# MX4-7-9-ESP12.net
KiCad netlist of a schematic drawn in EAGLE
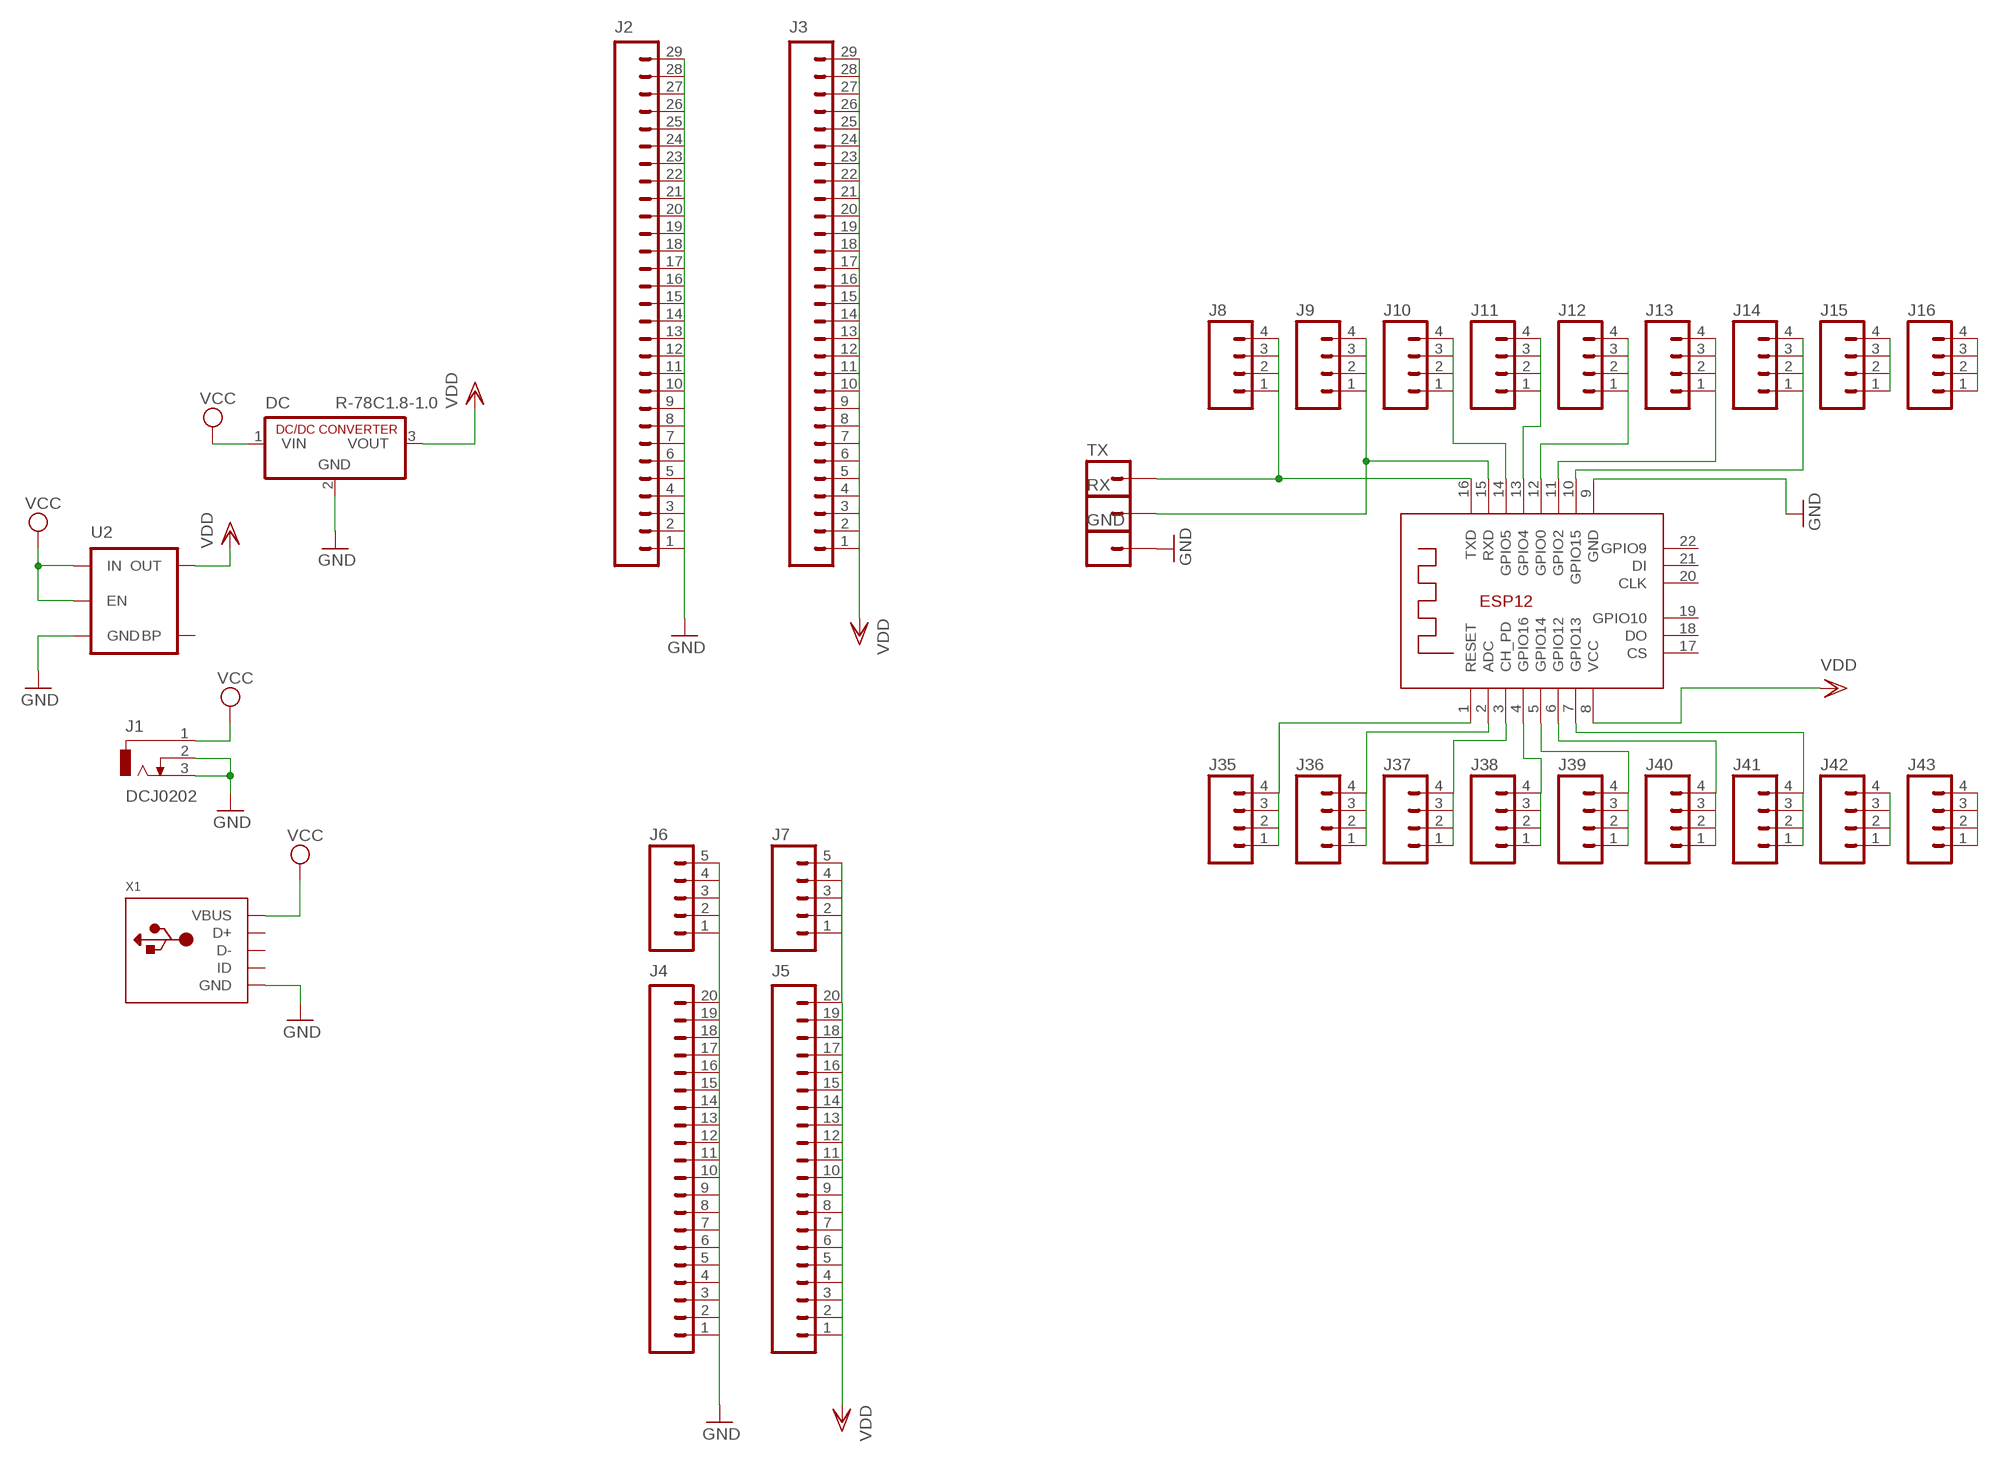
[diagram p0: schematic, sheet 1, part 1 of 2]
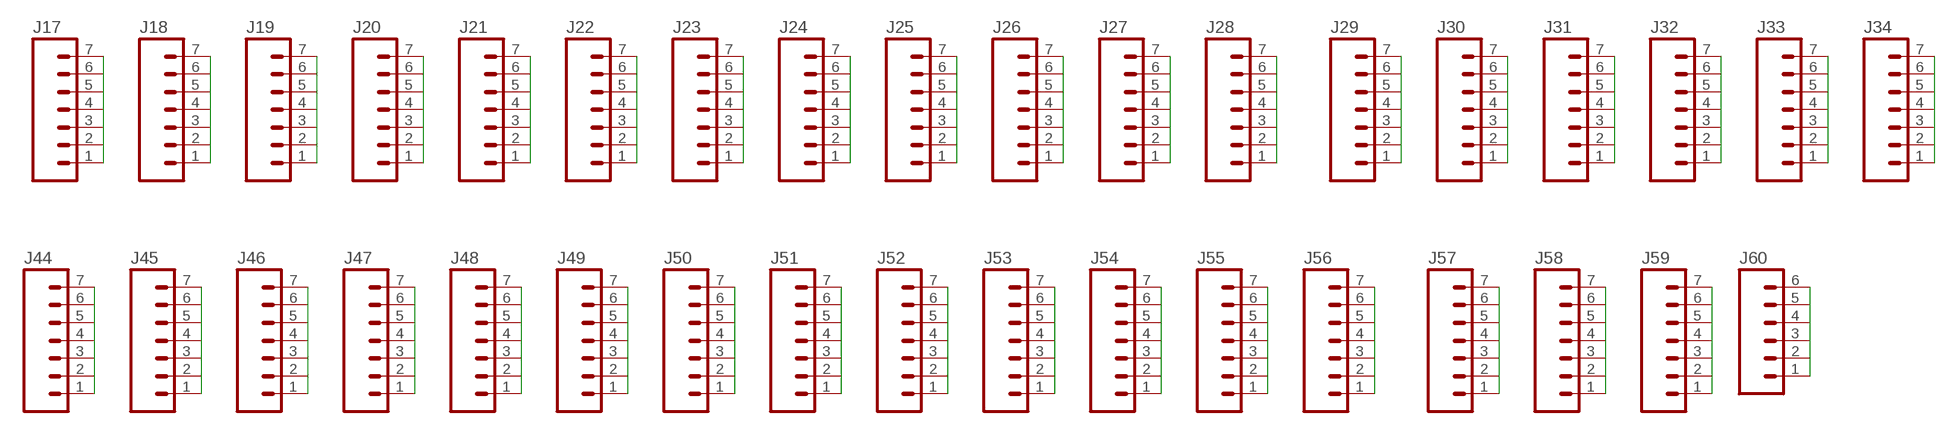
[diagram p1: schematic, sheet 1, part 2 of 2]

(export (version "E")
  (design (tool "Eeschema 10.0.6"))
  (components
    (comp (ref "DC")
      (value "R-78C1.8-1.0")
      (footprint "eagle-import:SIP3")
      (libsource (lib "eagle-import") (part "R-78C-1.01.8"))
    )
    (comp (ref "GND")
      (value "M01PTH_NO_SILK_YES_STOP")
      (footprint "eagle-import:1X01_NO_SILK")
      (libsource (lib "eagle-import") (part "M01PTH_NO_SILK_YES_STOP"))
    )
    (comp (ref "J1")
      (value "DCJ0202")
      (footprint "eagle-import:DCJ0202")
      (libsource (lib "eagle-import") (part "DCJ0202"))
    )
    (comp (ref "J2")
      (value "M29NO_SILK")
      (footprint "eagle-import:1X29_NO_SILK")
      (libsource (lib "eagle-import") (part "M29NO_SILK"))
    )
    (comp (ref "J3")
      (value "M29NO_SILK")
      (footprint "eagle-import:1X29_NO_SILK")
      (libsource (lib "eagle-import") (part "M29NO_SILK"))
    )
    (comp (ref "J4")
      (value "M20NO_SILK_KIT")
      (footprint "eagle-import:1X20_NO_SILK_KIT")
      (libsource (lib "eagle-import") (part "M20NO_SILK_KIT"))
    )
    (comp (ref "J5")
      (value "M20NO_SILK_KIT")
      (footprint "eagle-import:1X20_NO_SILK_KIT")
      (libsource (lib "eagle-import") (part "M20NO_SILK_KIT"))
    )
    (comp (ref "J6")
      (value "M05NO_SILK")
      (footprint "eagle-import:1X05_NO_SILK")
      (libsource (lib "eagle-import") (part "M05NO_SILK"))
    )
    (comp (ref "J7")
      (value "M05NO_SILK")
      (footprint "eagle-import:1X05_NO_SILK")
      (libsource (lib "eagle-import") (part "M05NO_SILK"))
    )
    (comp (ref "J8")
      (value "M04NO_SILK_ALL_ROUND")
      (footprint "eagle-import:1X04_NO_SILK_ALL_ROUND")
      (libsource (lib "eagle-import") (part "M04NO_SILK_ALL_ROUND"))
    )
    (comp (ref "J9")
      (value "M04NO_SILK_ALL_ROUND")
      (footprint "eagle-import:1X04_NO_SILK_ALL_ROUND")
      (libsource (lib "eagle-import") (part "M04NO_SILK_ALL_ROUND"))
    )
    (comp (ref "J10")
      (value "M04NO_SILK_ALL_ROUND")
      (footprint "eagle-import:1X04_NO_SILK_ALL_ROUND")
      (libsource (lib "eagle-import") (part "M04NO_SILK_ALL_ROUND"))
    )
    (comp (ref "J11")
      (value "M04NO_SILK_ALL_ROUND")
      (footprint "eagle-import:1X04_NO_SILK_ALL_ROUND")
      (libsource (lib "eagle-import") (part "M04NO_SILK_ALL_ROUND"))
    )
    (comp (ref "J12")
      (value "M04NO_SILK_ALL_ROUND")
      (footprint "eagle-import:1X04_NO_SILK_ALL_ROUND")
      (libsource (lib "eagle-import") (part "M04NO_SILK_ALL_ROUND"))
    )
    (comp (ref "J13")
      (value "M04NO_SILK_ALL_ROUND")
      (footprint "eagle-import:1X04_NO_SILK_ALL_ROUND")
      (libsource (lib "eagle-import") (part "M04NO_SILK_ALL_ROUND"))
    )
    (comp (ref "J14")
      (value "M04NO_SILK_ALL_ROUND")
      (footprint "eagle-import:1X04_NO_SILK_ALL_ROUND")
      (libsource (lib "eagle-import") (part "M04NO_SILK_ALL_ROUND"))
    )
    (comp (ref "J15")
      (value "M04NO_SILK_ALL_ROUND")
      (footprint "eagle-import:1X04_NO_SILK_ALL_ROUND")
      (libsource (lib "eagle-import") (part "M04NO_SILK_ALL_ROUND"))
    )
    (comp (ref "J16")
      (value "M04NO_SILK_ALL_ROUND")
      (footprint "eagle-import:1X04_NO_SILK_ALL_ROUND")
      (libsource (lib "eagle-import") (part "M04NO_SILK_ALL_ROUND"))
    )
    (comp (ref "J17")
      (value "M07NO_SILK")
      (footprint "eagle-import:1X07_NO_SILK")
      (libsource (lib "eagle-import") (part "M07NO_SILK"))
    )
    (comp (ref "J18")
      (value "M07NO_SILK")
      (footprint "eagle-import:1X07_NO_SILK")
      (libsource (lib "eagle-import") (part "M07NO_SILK"))
    )
    (comp (ref "J19")
      (value "M07NO_SILK")
      (footprint "eagle-import:1X07_NO_SILK")
      (libsource (lib "eagle-import") (part "M07NO_SILK"))
    )
    (comp (ref "J20")
      (value "M07NO_SILK")
      (footprint "eagle-import:1X07_NO_SILK")
      (libsource (lib "eagle-import") (part "M07NO_SILK"))
    )
    (comp (ref "J21")
      (value "M07NO_SILK")
      (footprint "eagle-import:1X07_NO_SILK")
      (libsource (lib "eagle-import") (part "M07NO_SILK"))
    )
    (comp (ref "J22")
      (value "M07NO_SILK")
      (footprint "eagle-import:1X07_NO_SILK")
      (libsource (lib "eagle-import") (part "M07NO_SILK"))
    )
    (comp (ref "J23")
      (value "M07NO_SILK")
      (footprint "eagle-import:1X07_NO_SILK")
      (libsource (lib "eagle-import") (part "M07NO_SILK"))
    )
    (comp (ref "J24")
      (value "M07NO_SILK")
      (footprint "eagle-import:1X07_NO_SILK")
      (libsource (lib "eagle-import") (part "M07NO_SILK"))
    )
    (comp (ref "J25")
      (value "M07NO_SILK")
      (footprint "eagle-import:1X07_NO_SILK")
      (libsource (lib "eagle-import") (part "M07NO_SILK"))
    )
    (comp (ref "J26")
      (value "M07NO_SILK")
      (footprint "eagle-import:1X07_NO_SILK")
      (libsource (lib "eagle-import") (part "M07NO_SILK"))
    )
    (comp (ref "J27")
      (value "M07NO_SILK")
      (footprint "eagle-import:1X07_NO_SILK")
      (libsource (lib "eagle-import") (part "M07NO_SILK"))
    )
    (comp (ref "J28")
      (value "M07NO_SILK")
      (footprint "eagle-import:1X07_NO_SILK")
      (libsource (lib "eagle-import") (part "M07NO_SILK"))
    )
    (comp (ref "J29")
      (value "M07NO_SILK")
      (footprint "eagle-import:1X07_NO_SILK")
      (libsource (lib "eagle-import") (part "M07NO_SILK"))
    )
    (comp (ref "J30")
      (value "M07NO_SILK")
      (footprint "eagle-import:1X07_NO_SILK")
      (libsource (lib "eagle-import") (part "M07NO_SILK"))
    )
    (comp (ref "J31")
      (value "M07NO_SILK")
      (footprint "eagle-import:1X07_NO_SILK")
      (libsource (lib "eagle-import") (part "M07NO_SILK"))
    )
    (comp (ref "J32")
      (value "M07NO_SILK")
      (footprint "eagle-import:1X07_NO_SILK")
      (libsource (lib "eagle-import") (part "M07NO_SILK"))
    )
    (comp (ref "J33")
      (value "M07NO_SILK")
      (footprint "eagle-import:1X07_NO_SILK")
      (libsource (lib "eagle-import") (part "M07NO_SILK"))
    )
    (comp (ref "J34")
      (value "M07NO_SILK")
      (footprint "eagle-import:1X07_NO_SILK")
      (libsource (lib "eagle-import") (part "M07NO_SILK"))
    )
    (comp (ref "J35")
      (value "M04NO_SILK_ALL_ROUND")
      (footprint "eagle-import:1X04_NO_SILK_ALL_ROUND")
      (libsource (lib "eagle-import") (part "M04NO_SILK_ALL_ROUND"))
    )
    (comp (ref "J36")
      (value "M04NO_SILK_ALL_ROUND")
      (footprint "eagle-import:1X04_NO_SILK_ALL_ROUND")
      (libsource (lib "eagle-import") (part "M04NO_SILK_ALL_ROUND"))
    )
    (comp (ref "J37")
      (value "M04NO_SILK_ALL_ROUND")
      (footprint "eagle-import:1X04_NO_SILK_ALL_ROUND")
      (libsource (lib "eagle-import") (part "M04NO_SILK_ALL_ROUND"))
    )
    (comp (ref "J38")
      (value "M04NO_SILK_ALL_ROUND")
      (footprint "eagle-import:1X04_NO_SILK_ALL_ROUND")
      (libsource (lib "eagle-import") (part "M04NO_SILK_ALL_ROUND"))
    )
    (comp (ref "J39")
      (value "M04NO_SILK_ALL_ROUND")
      (footprint "eagle-import:1X04_NO_SILK_ALL_ROUND")
      (libsource (lib "eagle-import") (part "M04NO_SILK_ALL_ROUND"))
    )
    (comp (ref "J40")
      (value "M04NO_SILK_ALL_ROUND")
      (footprint "eagle-import:1X04_NO_SILK_ALL_ROUND")
      (libsource (lib "eagle-import") (part "M04NO_SILK_ALL_ROUND"))
    )
    (comp (ref "J41")
      (value "M04NO_SILK_ALL_ROUND")
      (footprint "eagle-import:1X04_NO_SILK_ALL_ROUND")
      (libsource (lib "eagle-import") (part "M04NO_SILK_ALL_ROUND"))
    )
    (comp (ref "J42")
      (value "M04NO_SILK_ALL_ROUND")
      (footprint "eagle-import:1X04_NO_SILK_ALL_ROUND")
      (libsource (lib "eagle-import") (part "M04NO_SILK_ALL_ROUND"))
    )
    (comp (ref "J43")
      (value "M04NO_SILK_ALL_ROUND")
      (footprint "eagle-import:1X04_NO_SILK_ALL_ROUND")
      (libsource (lib "eagle-import") (part "M04NO_SILK_ALL_ROUND"))
    )
    (comp (ref "J44")
      (value "M07NO_SILK")
      (footprint "eagle-import:1X07_NO_SILK")
      (libsource (lib "eagle-import") (part "M07NO_SILK"))
    )
    (comp (ref "J45")
      (value "M07NO_SILK")
      (footprint "eagle-import:1X07_NO_SILK")
      (libsource (lib "eagle-import") (part "M07NO_SILK"))
    )
    (comp (ref "J46")
      (value "M07NO_SILK")
      (footprint "eagle-import:1X07_NO_SILK")
      (libsource (lib "eagle-import") (part "M07NO_SILK"))
    )
    (comp (ref "J47")
      (value "M07NO_SILK")
      (footprint "eagle-import:1X07_NO_SILK")
      (libsource (lib "eagle-import") (part "M07NO_SILK"))
    )
    (comp (ref "J48")
      (value "M07NO_SILK")
      (footprint "eagle-import:1X07_NO_SILK")
      (libsource (lib "eagle-import") (part "M07NO_SILK"))
    )
    (comp (ref "J49")
      (value "M07NO_SILK")
      (footprint "eagle-import:1X07_NO_SILK")
      (libsource (lib "eagle-import") (part "M07NO_SILK"))
    )
    (comp (ref "J50")
      (value "M07NO_SILK")
      (footprint "eagle-import:1X07_NO_SILK")
      (libsource (lib "eagle-import") (part "M07NO_SILK"))
    )
    (comp (ref "J51")
      (value "M07NO_SILK")
      (footprint "eagle-import:1X07_NO_SILK")
      (libsource (lib "eagle-import") (part "M07NO_SILK"))
    )
    (comp (ref "J52")
      (value "M07NO_SILK")
      (footprint "eagle-import:1X07_NO_SILK")
      (libsource (lib "eagle-import") (part "M07NO_SILK"))
    )
    (comp (ref "J53")
      (value "M07NO_SILK")
      (footprint "eagle-import:1X07_NO_SILK")
      (libsource (lib "eagle-import") (part "M07NO_SILK"))
    )
    (comp (ref "J54")
      (value "M07NO_SILK")
      (footprint "eagle-import:1X07_NO_SILK")
      (libsource (lib "eagle-import") (part "M07NO_SILK"))
    )
    (comp (ref "J55")
      (value "M07NO_SILK")
      (footprint "eagle-import:1X07_NO_SILK")
      (libsource (lib "eagle-import") (part "M07NO_SILK"))
    )
    (comp (ref "J56")
      (value "M07NO_SILK")
      (footprint "eagle-import:1X07_NO_SILK")
      (libsource (lib "eagle-import") (part "M07NO_SILK"))
    )
    (comp (ref "J57")
      (value "M07NO_SILK")
      (footprint "eagle-import:1X07_NO_SILK")
      (libsource (lib "eagle-import") (part "M07NO_SILK"))
    )
    (comp (ref "J58")
      (value "M07NO_SILK")
      (footprint "eagle-import:1X07_NO_SILK")
      (libsource (lib "eagle-import") (part "M07NO_SILK"))
    )
    (comp (ref "J59")
      (value "M07NO_SILK")
      (footprint "eagle-import:1X07_NO_SILK")
      (libsource (lib "eagle-import") (part "M07NO_SILK"))
    )
    (comp (ref "J60")
      (value "M06NO_SILK_FEMALE_PTH")
      (footprint "eagle-import:1X06_NO_SILK")
      (libsource (lib "eagle-import") (part "M06NO_SILK_FEMALE_PTH"))
    )
    (comp (ref "RX")
      (value "M01PTH_NO_SILK_YES_STOP")
      (footprint "eagle-import:1X01_NO_SILK")
      (libsource (lib "eagle-import") (part "M01PTH_NO_SILK_YES_STOP"))
    )
    (comp (ref "TX")
      (value "M01PTH_NO_SILK_YES_STOP")
      (footprint "eagle-import:1X01_NO_SILK")
      (libsource (lib "eagle-import") (part "M01PTH_NO_SILK_YES_STOP"))
    )
    (comp (ref "U2")
      (value "MIC52053.3V")
      (footprint "eagle-import:SOT23-5")
      (libsource (lib "eagle-import") (part "MIC52053.3V"))
    )
    (comp (ref "X1")
      (value "USBMICRO_20329")
      (footprint "eagle-import:4UCONN_20329")
      (libsource (lib "eagle-import") (part "USBMICRO_20329"))
    )
    (comp (ref "X2")
      (value "ESP-12E")
      (footprint "eagle-import:ESP-12E")
      (libsource (lib "eagle-import") (part "ESP-12E"))
    )
  )
  (nets
    (net (code "1") (name "GND") (class "Default")
      (node (ref "DC") (pin "2") (pinfunction "GND_2") (pintype "passive"))
      (node (ref "GND") (pin "1") (pinfunction "1_1") (pintype "passive"))
      (node (ref "J1") (pin "2") (pinfunction "2_2") (pintype "passive"))
      (node (ref "J1") (pin "3") (pinfunction "3_3") (pintype "passive"))
      (node (ref "J2") (pin "1") (pinfunction "1_1") (pintype "passive"))
      (node (ref "J2") (pin "10") (pinfunction "10_10") (pintype "passive"))
      (node (ref "J2") (pin "11") (pinfunction "11_11") (pintype "passive"))
      (node (ref "J2") (pin "12") (pinfunction "12_12") (pintype "passive"))
      (node (ref "J2") (pin "13") (pinfunction "13_13") (pintype "passive"))
      (node (ref "J2") (pin "14") (pinfunction "14_14") (pintype "passive"))
      (node (ref "J2") (pin "15") (pinfunction "15_15") (pintype "passive"))
      (node (ref "J2") (pin "16") (pinfunction "16_16") (pintype "passive"))
      (node (ref "J2") (pin "17") (pinfunction "17_17") (pintype "passive"))
      (node (ref "J2") (pin "18") (pinfunction "18_18") (pintype "passive"))
      (node (ref "J2") (pin "19") (pinfunction "19_19") (pintype "passive"))
      (node (ref "J2") (pin "2") (pinfunction "2_2") (pintype "passive"))
      (node (ref "J2") (pin "20") (pinfunction "20_20") (pintype "passive"))
      (node (ref "J2") (pin "21") (pinfunction "21_21") (pintype "passive"))
      (node (ref "J2") (pin "22") (pinfunction "22_22") (pintype "passive"))
      (node (ref "J2") (pin "23") (pinfunction "23_23") (pintype "passive"))
      (node (ref "J2") (pin "24") (pinfunction "24_24") (pintype "passive"))
      (node (ref "J2") (pin "25") (pinfunction "25_25") (pintype "passive"))
      (node (ref "J2") (pin "26") (pinfunction "26_26") (pintype "passive"))
      (node (ref "J2") (pin "27") (pinfunction "27_27") (pintype "passive"))
      (node (ref "J2") (pin "28") (pinfunction "28_28") (pintype "passive"))
      (node (ref "J2") (pin "29") (pinfunction "29_29") (pintype "passive"))
      (node (ref "J2") (pin "3") (pinfunction "3_3") (pintype "passive"))
      (node (ref "J2") (pin "4") (pinfunction "4_4") (pintype "passive"))
      (node (ref "J2") (pin "5") (pinfunction "5_5") (pintype "passive"))
      (node (ref "J2") (pin "6") (pinfunction "6_6") (pintype "passive"))
      (node (ref "J2") (pin "7") (pinfunction "7_7") (pintype "passive"))
      (node (ref "J2") (pin "8") (pinfunction "8_8") (pintype "passive"))
      (node (ref "J2") (pin "9") (pinfunction "9_9") (pintype "passive"))
      (node (ref "J4") (pin "1") (pinfunction "1_1") (pintype "passive"))
      (node (ref "J4") (pin "10") (pinfunction "10_10") (pintype "passive"))
      (node (ref "J4") (pin "11") (pinfunction "11_11") (pintype "passive"))
      (node (ref "J4") (pin "12") (pinfunction "12_12") (pintype "passive"))
      (node (ref "J4") (pin "13") (pinfunction "13_13") (pintype "passive"))
      (node (ref "J4") (pin "14") (pinfunction "14_14") (pintype "passive"))
      (node (ref "J4") (pin "15") (pinfunction "15_15") (pintype "passive"))
      (node (ref "J4") (pin "16") (pinfunction "16_16") (pintype "passive"))
      (node (ref "J4") (pin "17") (pinfunction "17_17") (pintype "passive"))
      (node (ref "J4") (pin "18") (pinfunction "18_18") (pintype "passive"))
      (node (ref "J4") (pin "19") (pinfunction "19_19") (pintype "passive"))
      (node (ref "J4") (pin "2") (pinfunction "2_2") (pintype "passive"))
      (node (ref "J4") (pin "20") (pinfunction "20_20") (pintype "passive"))
      (node (ref "J4") (pin "3") (pinfunction "3_3") (pintype "passive"))
      (node (ref "J4") (pin "4") (pinfunction "4_4") (pintype "passive"))
      (node (ref "J4") (pin "5") (pinfunction "5_5") (pintype "passive"))
      (node (ref "J4") (pin "6") (pinfunction "6_6") (pintype "passive"))
      (node (ref "J4") (pin "7") (pinfunction "7_7") (pintype "passive"))
      (node (ref "J4") (pin "8") (pinfunction "8_8") (pintype "passive"))
      (node (ref "J4") (pin "9") (pinfunction "9_9") (pintype "passive"))
      (node (ref "J6") (pin "1") (pinfunction "1_1") (pintype "passive"))
      (node (ref "J6") (pin "2") (pinfunction "2_2") (pintype "passive"))
      (node (ref "J6") (pin "3") (pinfunction "3_3") (pintype "passive"))
      (node (ref "J6") (pin "4") (pinfunction "4_4") (pintype "passive"))
      (node (ref "J6") (pin "5") (pinfunction "5_5") (pintype "passive"))
      (node (ref "U2") (pin "2") (pinfunction "GND_2") (pintype "input"))
      (node (ref "X1") (pin "BASE@1") (pinfunction "GND_BASE@1") (pintype "power_in"))
      (node (ref "X1") (pin "BASE@2") (pinfunction "GND_BASE@2") (pintype "power_in"))
      (node (ref "X1") (pin "GND") (pinfunction "GND_GND") (pintype "power_in"))
      (node (ref "X1") (pin "SPRT@1") (pinfunction "GND_SPRT@1") (pintype "power_in"))
      (node (ref "X1") (pin "SPRT@2") (pinfunction "GND_SPRT@2") (pintype "power_in"))
      (node (ref "X1") (pin "SPRT@3") (pinfunction "GND_SPRT@3") (pintype "power_in"))
      (node (ref "X1") (pin "SPRT@4") (pinfunction "GND_SPRT@4") (pintype "power_in"))
      (node (ref "X2") (pin "9") (pinfunction "GND_9") (pintype "power_in"))
    )
    (net (code "2") (name "Net-(J15-Pad1)") (class "Default")
      (node (ref "J15") (pin "1") (pinfunction "1_1") (pintype "passive"))
      (node (ref "J15") (pin "2") (pinfunction "2_2") (pintype "passive"))
      (node (ref "J15") (pin "3") (pinfunction "3_3") (pintype "passive"))
      (node (ref "J15") (pin "4") (pinfunction "4_4") (pintype "passive"))
    )
    (net (code "3") (name "Net-(J16-Pad1)") (class "Default")
      (node (ref "J16") (pin "1") (pinfunction "1_1") (pintype "passive"))
      (node (ref "J16") (pin "2") (pinfunction "2_2") (pintype "passive"))
      (node (ref "J16") (pin "3") (pinfunction "3_3") (pintype "passive"))
      (node (ref "J16") (pin "4") (pinfunction "4_4") (pintype "passive"))
    )
    (net (code "4") (name "Net-(J17-Pad1)") (class "Default")
      (node (ref "J17") (pin "1") (pinfunction "1_1") (pintype "passive"))
      (node (ref "J17") (pin "2") (pinfunction "2_2") (pintype "passive"))
      (node (ref "J17") (pin "3") (pinfunction "3_3") (pintype "passive"))
      (node (ref "J17") (pin "4") (pinfunction "4_4") (pintype "passive"))
      (node (ref "J17") (pin "5") (pinfunction "5_5") (pintype "passive"))
      (node (ref "J17") (pin "6") (pinfunction "6_6") (pintype "passive"))
      (node (ref "J17") (pin "7") (pinfunction "7_7") (pintype "passive"))
    )
    (net (code "5") (name "Net-(J18-Pad1)") (class "Default")
      (node (ref "J18") (pin "1") (pinfunction "1_1") (pintype "passive"))
      (node (ref "J18") (pin "2") (pinfunction "2_2") (pintype "passive"))
      (node (ref "J18") (pin "3") (pinfunction "3_3") (pintype "passive"))
      (node (ref "J18") (pin "4") (pinfunction "4_4") (pintype "passive"))
      (node (ref "J18") (pin "5") (pinfunction "5_5") (pintype "passive"))
      (node (ref "J18") (pin "6") (pinfunction "6_6") (pintype "passive"))
      (node (ref "J18") (pin "7") (pinfunction "7_7") (pintype "passive"))
    )
    (net (code "6") (name "Net-(J19-Pad1)") (class "Default")
      (node (ref "J19") (pin "1") (pinfunction "1_1") (pintype "passive"))
      (node (ref "J19") (pin "2") (pinfunction "2_2") (pintype "passive"))
      (node (ref "J19") (pin "3") (pinfunction "3_3") (pintype "passive"))
      (node (ref "J19") (pin "4") (pinfunction "4_4") (pintype "passive"))
      (node (ref "J19") (pin "5") (pinfunction "5_5") (pintype "passive"))
      (node (ref "J19") (pin "6") (pinfunction "6_6") (pintype "passive"))
      (node (ref "J19") (pin "7") (pinfunction "7_7") (pintype "passive"))
    )
    (net (code "7") (name "Net-(J20-Pad1)") (class "Default")
      (node (ref "J20") (pin "1") (pinfunction "1_1") (pintype "passive"))
      (node (ref "J20") (pin "2") (pinfunction "2_2") (pintype "passive"))
      (node (ref "J20") (pin "3") (pinfunction "3_3") (pintype "passive"))
      (node (ref "J20") (pin "4") (pinfunction "4_4") (pintype "passive"))
      (node (ref "J20") (pin "5") (pinfunction "5_5") (pintype "passive"))
      (node (ref "J20") (pin "6") (pinfunction "6_6") (pintype "passive"))
      (node (ref "J20") (pin "7") (pinfunction "7_7") (pintype "passive"))
    )
    (net (code "8") (name "Net-(J21-Pad1)") (class "Default")
      (node (ref "J21") (pin "1") (pinfunction "1_1") (pintype "passive"))
      (node (ref "J21") (pin "2") (pinfunction "2_2") (pintype "passive"))
      (node (ref "J21") (pin "3") (pinfunction "3_3") (pintype "passive"))
      (node (ref "J21") (pin "4") (pinfunction "4_4") (pintype "passive"))
      (node (ref "J21") (pin "5") (pinfunction "5_5") (pintype "passive"))
      (node (ref "J21") (pin "6") (pinfunction "6_6") (pintype "passive"))
      (node (ref "J21") (pin "7") (pinfunction "7_7") (pintype "passive"))
    )
    (net (code "9") (name "Net-(J22-Pad1)") (class "Default")
      (node (ref "J22") (pin "1") (pinfunction "1_1") (pintype "passive"))
      (node (ref "J22") (pin "2") (pinfunction "2_2") (pintype "passive"))
      (node (ref "J22") (pin "3") (pinfunction "3_3") (pintype "passive"))
      (node (ref "J22") (pin "4") (pinfunction "4_4") (pintype "passive"))
      (node (ref "J22") (pin "5") (pinfunction "5_5") (pintype "passive"))
      (node (ref "J22") (pin "6") (pinfunction "6_6") (pintype "passive"))
      (node (ref "J22") (pin "7") (pinfunction "7_7") (pintype "passive"))
    )
    (net (code "10") (name "Net-(J23-Pad1)") (class "Default")
      (node (ref "J23") (pin "1") (pinfunction "1_1") (pintype "passive"))
      (node (ref "J23") (pin "2") (pinfunction "2_2") (pintype "passive"))
      (node (ref "J23") (pin "3") (pinfunction "3_3") (pintype "passive"))
      (node (ref "J23") (pin "4") (pinfunction "4_4") (pintype "passive"))
      (node (ref "J23") (pin "5") (pinfunction "5_5") (pintype "passive"))
      (node (ref "J23") (pin "6") (pinfunction "6_6") (pintype "passive"))
      (node (ref "J23") (pin "7") (pinfunction "7_7") (pintype "passive"))
    )
    (net (code "11") (name "Net-(J24-Pad1)") (class "Default")
      (node (ref "J24") (pin "1") (pinfunction "1_1") (pintype "passive"))
      (node (ref "J24") (pin "2") (pinfunction "2_2") (pintype "passive"))
      (node (ref "J24") (pin "3") (pinfunction "3_3") (pintype "passive"))
      (node (ref "J24") (pin "4") (pinfunction "4_4") (pintype "passive"))
      (node (ref "J24") (pin "5") (pinfunction "5_5") (pintype "passive"))
      (node (ref "J24") (pin "6") (pinfunction "6_6") (pintype "passive"))
      (node (ref "J24") (pin "7") (pinfunction "7_7") (pintype "passive"))
    )
    (net (code "12") (name "Net-(J25-Pad1)") (class "Default")
      (node (ref "J25") (pin "1") (pinfunction "1_1") (pintype "passive"))
      (node (ref "J25") (pin "2") (pinfunction "2_2") (pintype "passive"))
      (node (ref "J25") (pin "3") (pinfunction "3_3") (pintype "passive"))
      (node (ref "J25") (pin "4") (pinfunction "4_4") (pintype "passive"))
      (node (ref "J25") (pin "5") (pinfunction "5_5") (pintype "passive"))
      (node (ref "J25") (pin "6") (pinfunction "6_6") (pintype "passive"))
      (node (ref "J25") (pin "7") (pinfunction "7_7") (pintype "passive"))
    )
    (net (code "13") (name "Net-(J26-Pad1)") (class "Default")
      (node (ref "J26") (pin "1") (pinfunction "1_1") (pintype "passive"))
      (node (ref "J26") (pin "2") (pinfunction "2_2") (pintype "passive"))
      (node (ref "J26") (pin "3") (pinfunction "3_3") (pintype "passive"))
      (node (ref "J26") (pin "4") (pinfunction "4_4") (pintype "passive"))
      (node (ref "J26") (pin "5") (pinfunction "5_5") (pintype "passive"))
      (node (ref "J26") (pin "6") (pinfunction "6_6") (pintype "passive"))
      (node (ref "J26") (pin "7") (pinfunction "7_7") (pintype "passive"))
    )
    (net (code "14") (name "Net-(J27-Pad1)") (class "Default")
      (node (ref "J27") (pin "1") (pinfunction "1_1") (pintype "passive"))
      (node (ref "J27") (pin "2") (pinfunction "2_2") (pintype "passive"))
      (node (ref "J27") (pin "3") (pinfunction "3_3") (pintype "passive"))
      (node (ref "J27") (pin "4") (pinfunction "4_4") (pintype "passive"))
      (node (ref "J27") (pin "5") (pinfunction "5_5") (pintype "passive"))
      (node (ref "J27") (pin "6") (pinfunction "6_6") (pintype "passive"))
      (node (ref "J27") (pin "7") (pinfunction "7_7") (pintype "passive"))
    )
    (net (code "15") (name "Net-(J28-Pad1)") (class "Default")
      (node (ref "J28") (pin "1") (pinfunction "1_1") (pintype "passive"))
      (node (ref "J28") (pin "2") (pinfunction "2_2") (pintype "passive"))
      (node (ref "J28") (pin "3") (pinfunction "3_3") (pintype "passive"))
      (node (ref "J28") (pin "4") (pinfunction "4_4") (pintype "passive"))
      (node (ref "J28") (pin "5") (pinfunction "5_5") (pintype "passive"))
      (node (ref "J28") (pin "6") (pinfunction "6_6") (pintype "passive"))
      (node (ref "J28") (pin "7") (pinfunction "7_7") (pintype "passive"))
    )
    (net (code "16") (name "Net-(J29-Pad1)") (class "Default")
      (node (ref "J29") (pin "1") (pinfunction "1_1") (pintype "passive"))
      (node (ref "J29") (pin "2") (pinfunction "2_2") (pintype "passive"))
      (node (ref "J29") (pin "3") (pinfunction "3_3") (pintype "passive"))
      (node (ref "J29") (pin "4") (pinfunction "4_4") (pintype "passive"))
      (node (ref "J29") (pin "5") (pinfunction "5_5") (pintype "passive"))
      (node (ref "J29") (pin "6") (pinfunction "6_6") (pintype "passive"))
      (node (ref "J29") (pin "7") (pinfunction "7_7") (pintype "passive"))
    )
    (net (code "17") (name "Net-(J30-Pad1)") (class "Default")
      (node (ref "J30") (pin "1") (pinfunction "1_1") (pintype "passive"))
      (node (ref "J30") (pin "2") (pinfunction "2_2") (pintype "passive"))
      (node (ref "J30") (pin "3") (pinfunction "3_3") (pintype "passive"))
      (node (ref "J30") (pin "4") (pinfunction "4_4") (pintype "passive"))
      (node (ref "J30") (pin "5") (pinfunction "5_5") (pintype "passive"))
      (node (ref "J30") (pin "6") (pinfunction "6_6") (pintype "passive"))
      (node (ref "J30") (pin "7") (pinfunction "7_7") (pintype "passive"))
    )
    (net (code "18") (name "Net-(J31-Pad1)") (class "Default")
      (node (ref "J31") (pin "1") (pinfunction "1_1") (pintype "passive"))
      (node (ref "J31") (pin "2") (pinfunction "2_2") (pintype "passive"))
      (node (ref "J31") (pin "3") (pinfunction "3_3") (pintype "passive"))
      (node (ref "J31") (pin "4") (pinfunction "4_4") (pintype "passive"))
      (node (ref "J31") (pin "5") (pinfunction "5_5") (pintype "passive"))
      (node (ref "J31") (pin "6") (pinfunction "6_6") (pintype "passive"))
      (node (ref "J31") (pin "7") (pinfunction "7_7") (pintype "passive"))
    )
    (net (code "19") (name "Net-(J32-Pad1)") (class "Default")
      (node (ref "J32") (pin "1") (pinfunction "1_1") (pintype "passive"))
      (node (ref "J32") (pin "2") (pinfunction "2_2") (pintype "passive"))
      (node (ref "J32") (pin "3") (pinfunction "3_3") (pintype "passive"))
      (node (ref "J32") (pin "4") (pinfunction "4_4") (pintype "passive"))
      (node (ref "J32") (pin "5") (pinfunction "5_5") (pintype "passive"))
      (node (ref "J32") (pin "6") (pinfunction "6_6") (pintype "passive"))
      (node (ref "J32") (pin "7") (pinfunction "7_7") (pintype "passive"))
    )
    (net (code "20") (name "Net-(J33-Pad1)") (class "Default")
      (node (ref "J33") (pin "1") (pinfunction "1_1") (pintype "passive"))
      (node (ref "J33") (pin "2") (pinfunction "2_2") (pintype "passive"))
      (node (ref "J33") (pin "3") (pinfunction "3_3") (pintype "passive"))
      (node (ref "J33") (pin "4") (pinfunction "4_4") (pintype "passive"))
      (node (ref "J33") (pin "5") (pinfunction "5_5") (pintype "passive"))
      (node (ref "J33") (pin "6") (pinfunction "6_6") (pintype "passive"))
      (node (ref "J33") (pin "7") (pinfunction "7_7") (pintype "passive"))
    )
    (net (code "21") (name "Net-(J34-Pad1)") (class "Default")
      (node (ref "J34") (pin "1") (pinfunction "1_1") (pintype "passive"))
      (node (ref "J34") (pin "2") (pinfunction "2_2") (pintype "passive"))
      (node (ref "J34") (pin "3") (pinfunction "3_3") (pintype "passive"))
      (node (ref "J34") (pin "4") (pinfunction "4_4") (pintype "passive"))
      (node (ref "J34") (pin "5") (pinfunction "5_5") (pintype "passive"))
      (node (ref "J34") (pin "6") (pinfunction "6_6") (pintype "passive"))
      (node (ref "J34") (pin "7") (pinfunction "7_7") (pintype "passive"))
    )
    (net (code "22") (name "Net-(J42-Pad1)") (class "Default")
      (node (ref "J42") (pin "1") (pinfunction "1_1") (pintype "passive"))
      (node (ref "J42") (pin "2") (pinfunction "2_2") (pintype "passive"))
      (node (ref "J42") (pin "3") (pinfunction "3_3") (pintype "passive"))
      (node (ref "J42") (pin "4") (pinfunction "4_4") (pintype "passive"))
    )
    (net (code "23") (name "Net-(J43-Pad1)") (class "Default")
      (node (ref "J43") (pin "1") (pinfunction "1_1") (pintype "passive"))
      (node (ref "J43") (pin "2") (pinfunction "2_2") (pintype "passive"))
      (node (ref "J43") (pin "3") (pinfunction "3_3") (pintype "passive"))
      (node (ref "J43") (pin "4") (pinfunction "4_4") (pintype "passive"))
    )
    (net (code "24") (name "Net-(J44-Pad1)") (class "Default")
      (node (ref "J44") (pin "1") (pinfunction "1_1") (pintype "passive"))
      (node (ref "J44") (pin "2") (pinfunction "2_2") (pintype "passive"))
      (node (ref "J44") (pin "3") (pinfunction "3_3") (pintype "passive"))
      (node (ref "J44") (pin "4") (pinfunction "4_4") (pintype "passive"))
      (node (ref "J44") (pin "5") (pinfunction "5_5") (pintype "passive"))
      (node (ref "J44") (pin "6") (pinfunction "6_6") (pintype "passive"))
      (node (ref "J44") (pin "7") (pinfunction "7_7") (pintype "passive"))
    )
    (net (code "25") (name "Net-(J45-Pad1)") (class "Default")
      (node (ref "J45") (pin "1") (pinfunction "1_1") (pintype "passive"))
      (node (ref "J45") (pin "2") (pinfunction "2_2") (pintype "passive"))
      (node (ref "J45") (pin "3") (pinfunction "3_3") (pintype "passive"))
      (node (ref "J45") (pin "4") (pinfunction "4_4") (pintype "passive"))
      (node (ref "J45") (pin "5") (pinfunction "5_5") (pintype "passive"))
      (node (ref "J45") (pin "6") (pinfunction "6_6") (pintype "passive"))
      (node (ref "J45") (pin "7") (pinfunction "7_7") (pintype "passive"))
    )
    (net (code "26") (name "Net-(J46-Pad1)") (class "Default")
      (node (ref "J46") (pin "1") (pinfunction "1_1") (pintype "passive"))
      (node (ref "J46") (pin "2") (pinfunction "2_2") (pintype "passive"))
      (node (ref "J46") (pin "3") (pinfunction "3_3") (pintype "passive"))
      (node (ref "J46") (pin "4") (pinfunction "4_4") (pintype "passive"))
      (node (ref "J46") (pin "5") (pinfunction "5_5") (pintype "passive"))
      (node (ref "J46") (pin "6") (pinfunction "6_6") (pintype "passive"))
      (node (ref "J46") (pin "7") (pinfunction "7_7") (pintype "passive"))
    )
    (net (code "27") (name "Net-(J47-Pad1)") (class "Default")
      (node (ref "J47") (pin "1") (pinfunction "1_1") (pintype "passive"))
      (node (ref "J47") (pin "2") (pinfunction "2_2") (pintype "passive"))
      (node (ref "J47") (pin "3") (pinfunction "3_3") (pintype "passive"))
      (node (ref "J47") (pin "4") (pinfunction "4_4") (pintype "passive"))
      (node (ref "J47") (pin "5") (pinfunction "5_5") (pintype "passive"))
      (node (ref "J47") (pin "6") (pinfunction "6_6") (pintype "passive"))
      (node (ref "J47") (pin "7") (pinfunction "7_7") (pintype "passive"))
    )
    (net (code "28") (name "Net-(J48-Pad1)") (class "Default")
      (node (ref "J48") (pin "1") (pinfunction "1_1") (pintype "passive"))
      (node (ref "J48") (pin "2") (pinfunction "2_2") (pintype "passive"))
      (node (ref "J48") (pin "3") (pinfunction "3_3") (pintype "passive"))
      (node (ref "J48") (pin "4") (pinfunction "4_4") (pintype "passive"))
      (node (ref "J48") (pin "5") (pinfunction "5_5") (pintype "passive"))
      (node (ref "J48") (pin "6") (pinfunction "6_6") (pintype "passive"))
      (node (ref "J48") (pin "7") (pinfunction "7_7") (pintype "passive"))
    )
    (net (code "29") (name "Net-(J49-Pad1)") (class "Default")
      (node (ref "J49") (pin "1") (pinfunction "1_1") (pintype "passive"))
      (node (ref "J49") (pin "2") (pinfunction "2_2") (pintype "passive"))
      (node (ref "J49") (pin "3") (pinfunction "3_3") (pintype "passive"))
      (node (ref "J49") (pin "4") (pinfunction "4_4") (pintype "passive"))
      (node (ref "J49") (pin "5") (pinfunction "5_5") (pintype "passive"))
      (node (ref "J49") (pin "6") (pinfunction "6_6") (pintype "passive"))
      (node (ref "J49") (pin "7") (pinfunction "7_7") (pintype "passive"))
    )
    (net (code "30") (name "Net-(J50-Pad1)") (class "Default")
      (node (ref "J50") (pin "1") (pinfunction "1_1") (pintype "passive"))
      (node (ref "J50") (pin "2") (pinfunction "2_2") (pintype "passive"))
      (node (ref "J50") (pin "3") (pinfunction "3_3") (pintype "passive"))
      (node (ref "J50") (pin "4") (pinfunction "4_4") (pintype "passive"))
      (node (ref "J50") (pin "5") (pinfunction "5_5") (pintype "passive"))
      (node (ref "J50") (pin "6") (pinfunction "6_6") (pintype "passive"))
      (node (ref "J50") (pin "7") (pinfunction "7_7") (pintype "passive"))
    )
    (net (code "31") (name "Net-(J51-Pad1)") (class "Default")
      (node (ref "J51") (pin "1") (pinfunction "1_1") (pintype "passive"))
      (node (ref "J51") (pin "2") (pinfunction "2_2") (pintype "passive"))
      (node (ref "J51") (pin "3") (pinfunction "3_3") (pintype "passive"))
      (node (ref "J51") (pin "4") (pinfunction "4_4") (pintype "passive"))
      (node (ref "J51") (pin "5") (pinfunction "5_5") (pintype "passive"))
      (node (ref "J51") (pin "6") (pinfunction "6_6") (pintype "passive"))
      (node (ref "J51") (pin "7") (pinfunction "7_7") (pintype "passive"))
    )
    (net (code "32") (name "Net-(J52-Pad1)") (class "Default")
      (node (ref "J52") (pin "1") (pinfunction "1_1") (pintype "passive"))
      (node (ref "J52") (pin "2") (pinfunction "2_2") (pintype "passive"))
      (node (ref "J52") (pin "3") (pinfunction "3_3") (pintype "passive"))
      (node (ref "J52") (pin "4") (pinfunction "4_4") (pintype "passive"))
      (node (ref "J52") (pin "5") (pinfunction "5_5") (pintype "passive"))
      (node (ref "J52") (pin "6") (pinfunction "6_6") (pintype "passive"))
      (node (ref "J52") (pin "7") (pinfunction "7_7") (pintype "passive"))
    )
    (net (code "33") (name "Net-(J53-Pad1)") (class "Default")
      (node (ref "J53") (pin "1") (pinfunction "1_1") (pintype "passive"))
      (node (ref "J53") (pin "2") (pinfunction "2_2") (pintype "passive"))
      (node (ref "J53") (pin "3") (pinfunction "3_3") (pintype "passive"))
      (node (ref "J53") (pin "4") (pinfunction "4_4") (pintype "passive"))
      (node (ref "J53") (pin "5") (pinfunction "5_5") (pintype "passive"))
      (node (ref "J53") (pin "6") (pinfunction "6_6") (pintype "passive"))
      (node (ref "J53") (pin "7") (pinfunction "7_7") (pintype "passive"))
    )
    (net (code "34") (name "Net-(J54-Pad1)") (class "Default")
      (node (ref "J54") (pin "1") (pinfunction "1_1") (pintype "passive"))
      (node (ref "J54") (pin "2") (pinfunction "2_2") (pintype "passive"))
      (node (ref "J54") (pin "3") (pinfunction "3_3") (pintype "passive"))
      (node (ref "J54") (pin "4") (pinfunction "4_4") (pintype "passive"))
      (node (ref "J54") (pin "5") (pinfunction "5_5") (pintype "passive"))
      (node (ref "J54") (pin "6") (pinfunction "6_6") (pintype "passive"))
      (node (ref "J54") (pin "7") (pinfunction "7_7") (pintype "passive"))
    )
    (net (code "35") (name "Net-(J55-Pad1)") (class "Default")
      (node (ref "J55") (pin "1") (pinfunction "1_1") (pintype "passive"))
      (node (ref "J55") (pin "2") (pinfunction "2_2") (pintype "passive"))
      (node (ref "J55") (pin "3") (pinfunction "3_3") (pintype "passive"))
      (node (ref "J55") (pin "4") (pinfunction "4_4") (pintype "passive"))
      (node (ref "J55") (pin "5") (pinfunction "5_5") (pintype "passive"))
      (node (ref "J55") (pin "6") (pinfunction "6_6") (pintype "passive"))
      (node (ref "J55") (pin "7") (pinfunction "7_7") (pintype "passive"))
    )
    (net (code "36") (name "Net-(J56-Pad1)") (class "Default")
      (node (ref "J56") (pin "1") (pinfunction "1_1") (pintype "passive"))
      (node (ref "J56") (pin "2") (pinfunction "2_2") (pintype "passive"))
      (node (ref "J56") (pin "3") (pinfunction "3_3") (pintype "passive"))
      (node (ref "J56") (pin "4") (pinfunction "4_4") (pintype "passive"))
      (node (ref "J56") (pin "5") (pinfunction "5_5") (pintype "passive"))
      (node (ref "J56") (pin "6") (pinfunction "6_6") (pintype "passive"))
      (node (ref "J56") (pin "7") (pinfunction "7_7") (pintype "passive"))
    )
    (net (code "37") (name "Net-(J57-Pad1)") (class "Default")
      (node (ref "J57") (pin "1") (pinfunction "1_1") (pintype "passive"))
      (node (ref "J57") (pin "2") (pinfunction "2_2") (pintype "passive"))
      (node (ref "J57") (pin "3") (pinfunction "3_3") (pintype "passive"))
      (node (ref "J57") (pin "4") (pinfunction "4_4") (pintype "passive"))
      (node (ref "J57") (pin "5") (pinfunction "5_5") (pintype "passive"))
      (node (ref "J57") (pin "6") (pinfunction "6_6") (pintype "passive"))
      (node (ref "J57") (pin "7") (pinfunction "7_7") (pintype "passive"))
    )
    (net (code "38") (name "Net-(J58-Pad1)") (class "Default")
      (node (ref "J58") (pin "1") (pinfunction "1_1") (pintype "passive"))
      (node (ref "J58") (pin "2") (pinfunction "2_2") (pintype "passive"))
      (node (ref "J58") (pin "3") (pinfunction "3_3") (pintype "passive"))
      (node (ref "J58") (pin "4") (pinfunction "4_4") (pintype "passive"))
      (node (ref "J58") (pin "5") (pinfunction "5_5") (pintype "passive"))
      (node (ref "J58") (pin "6") (pinfunction "6_6") (pintype "passive"))
      (node (ref "J58") (pin "7") (pinfunction "7_7") (pintype "passive"))
    )
    (net (code "39") (name "Net-(J59-Pad1)") (class "Default")
      (node (ref "J59") (pin "1") (pinfunction "1_1") (pintype "passive"))
      (node (ref "J59") (pin "2") (pinfunction "2_2") (pintype "passive"))
      (node (ref "J59") (pin "3") (pinfunction "3_3") (pintype "passive"))
      (node (ref "J59") (pin "4") (pinfunction "4_4") (pintype "passive"))
      (node (ref "J59") (pin "5") (pinfunction "5_5") (pintype "passive"))
      (node (ref "J59") (pin "6") (pinfunction "6_6") (pintype "passive"))
      (node (ref "J59") (pin "7") (pinfunction "7_7") (pintype "passive"))
    )
    (net (code "40") (name "Net-(J60-Pad1)") (class "Default")
      (node (ref "J60") (pin "1") (pinfunction "1_1") (pintype "passive"))
      (node (ref "J60") (pin "2") (pinfunction "2_2") (pintype "passive"))
      (node (ref "J60") (pin "3") (pinfunction "3_3") (pintype "passive"))
      (node (ref "J60") (pin "4") (pinfunction "4_4") (pintype "passive"))
      (node (ref "J60") (pin "5") (pinfunction "5_5") (pintype "passive"))
      (node (ref "J60") (pin "6") (pinfunction "6_6") (pintype "passive"))
    )
    (net (code "41") (name "Net-(X2-ADC)") (class "Default")
      (node (ref "J36") (pin "1") (pinfunction "1_1") (pintype "passive"))
      (node (ref "J36") (pin "2") (pinfunction "2_2") (pintype "passive"))
      (node (ref "J36") (pin "3") (pinfunction "3_3") (pintype "passive"))
      (node (ref "J36") (pin "4") (pinfunction "4_4") (pintype "passive"))
      (node (ref "X2") (pin "2") (pinfunction "ADC_2") (pintype "passive"))
    )
    (net (code "42") (name "Net-(X2-CH_PD)") (class "Default")
      (node (ref "J37") (pin "1") (pinfunction "1_1") (pintype "passive"))
      (node (ref "J37") (pin "2") (pinfunction "2_2") (pintype "passive"))
      (node (ref "J37") (pin "3") (pinfunction "3_3") (pintype "passive"))
      (node (ref "J37") (pin "4") (pinfunction "4_4") (pintype "passive"))
      (node (ref "X2") (pin "3") (pinfunction "CH_PD_3") (pintype "input"))
    )
    (net (code "43") (name "Net-(X2-GPIO0)") (class "Default")
      (node (ref "J12") (pin "1") (pinfunction "1_1") (pintype "passive"))
      (node (ref "J12") (pin "2") (pinfunction "2_2") (pintype "passive"))
      (node (ref "J12") (pin "3") (pinfunction "3_3") (pintype "passive"))
      (node (ref "J12") (pin "4") (pinfunction "4_4") (pintype "passive"))
      (node (ref "X2") (pin "12") (pinfunction "GPIO0_12") (pintype "bidirectional"))
    )
    (net (code "44") (name "Net-(X2-GPIO2)") (class "Default")
      (node (ref "J13") (pin "1") (pinfunction "1_1") (pintype "passive"))
      (node (ref "J13") (pin "2") (pinfunction "2_2") (pintype "passive"))
      (node (ref "J13") (pin "3") (pinfunction "3_3") (pintype "passive"))
      (node (ref "J13") (pin "4") (pinfunction "4_4") (pintype "passive"))
      (node (ref "X2") (pin "11") (pinfunction "GPIO2_11") (pintype "bidirectional"))
    )
    (net (code "45") (name "Net-(X2-GPIO4)") (class "Default")
      (node (ref "J11") (pin "1") (pinfunction "1_1") (pintype "passive"))
      (node (ref "J11") (pin "2") (pinfunction "2_2") (pintype "passive"))
      (node (ref "J11") (pin "3") (pinfunction "3_3") (pintype "passive"))
      (node (ref "J11") (pin "4") (pinfunction "4_4") (pintype "passive"))
      (node (ref "X2") (pin "13") (pinfunction "GPIO4_13") (pintype "bidirectional"))
    )
    (net (code "46") (name "Net-(X2-GPIO5)") (class "Default")
      (node (ref "J10") (pin "1") (pinfunction "1_1") (pintype "passive"))
      (node (ref "J10") (pin "2") (pinfunction "2_2") (pintype "passive"))
      (node (ref "J10") (pin "3") (pinfunction "3_3") (pintype "passive"))
      (node (ref "J10") (pin "4") (pinfunction "4_4") (pintype "passive"))
      (node (ref "X2") (pin "14") (pinfunction "GPIO5_14") (pintype "bidirectional"))
    )
    (net (code "47") (name "Net-(X2-GPIO12)") (class "Default")
      (node (ref "J40") (pin "1") (pinfunction "1_1") (pintype "passive"))
      (node (ref "J40") (pin "2") (pinfunction "2_2") (pintype "passive"))
      (node (ref "J40") (pin "3") (pinfunction "3_3") (pintype "passive"))
      (node (ref "J40") (pin "4") (pinfunction "4_4") (pintype "passive"))
      (node (ref "X2") (pin "6") (pinfunction "GPIO12_6") (pintype "bidirectional"))
    )
    (net (code "48") (name "Net-(X2-GPIO13)") (class "Default")
      (node (ref "J41") (pin "1") (pinfunction "1_1") (pintype "passive"))
      (node (ref "J41") (pin "2") (pinfunction "2_2") (pintype "passive"))
      (node (ref "J41") (pin "3") (pinfunction "3_3") (pintype "passive"))
      (node (ref "J41") (pin "4") (pinfunction "4_4") (pintype "passive"))
      (node (ref "X2") (pin "7") (pinfunction "GPIO13_7") (pintype "bidirectional"))
    )
    (net (code "49") (name "Net-(X2-GPIO14)") (class "Default")
      (node (ref "J39") (pin "1") (pinfunction "1_1") (pintype "passive"))
      (node (ref "J39") (pin "2") (pinfunction "2_2") (pintype "passive"))
      (node (ref "J39") (pin "3") (pinfunction "3_3") (pintype "passive"))
      (node (ref "J39") (pin "4") (pinfunction "4_4") (pintype "passive"))
      (node (ref "X2") (pin "5") (pinfunction "GPIO14_5") (pintype "bidirectional"))
    )
    (net (code "50") (name "Net-(X2-GPIO15)") (class "Default")
      (node (ref "J14") (pin "1") (pinfunction "1_1") (pintype "passive"))
      (node (ref "J14") (pin "2") (pinfunction "2_2") (pintype "passive"))
      (node (ref "J14") (pin "3") (pinfunction "3_3") (pintype "passive"))
      (node (ref "J14") (pin "4") (pinfunction "4_4") (pintype "passive"))
      (node (ref "X2") (pin "10") (pinfunction "GPIO15_10") (pintype "bidirectional"))
    )
    (net (code "51") (name "Net-(X2-GPIO16)") (class "Default")
      (node (ref "J38") (pin "1") (pinfunction "1_1") (pintype "passive"))
      (node (ref "J38") (pin "2") (pinfunction "2_2") (pintype "passive"))
      (node (ref "J38") (pin "3") (pinfunction "3_3") (pintype "passive"))
      (node (ref "J38") (pin "4") (pinfunction "4_4") (pintype "passive"))
      (node (ref "X2") (pin "4") (pinfunction "GPIO16_4") (pintype "bidirectional"))
    )
    (net (code "52") (name "Net-(X2-RESET)") (class "Default")
      (node (ref "J35") (pin "1") (pinfunction "1_1") (pintype "passive"))
      (node (ref "J35") (pin "2") (pinfunction "2_2") (pintype "passive"))
      (node (ref "J35") (pin "3") (pinfunction "3_3") (pintype "passive"))
      (node (ref "J35") (pin "4") (pinfunction "4_4") (pintype "passive"))
      (node (ref "X2") (pin "1") (pinfunction "RESET_1") (pintype "input"))
    )
    (net (code "53") (name "Net-(X2-RXD)") (class "Default")
      (node (ref "J9") (pin "1") (pinfunction "1_1") (pintype "passive"))
      (node (ref "J9") (pin "2") (pinfunction "2_2") (pintype "passive"))
      (node (ref "J9") (pin "3") (pinfunction "3_3") (pintype "passive"))
      (node (ref "J9") (pin "4") (pinfunction "4_4") (pintype "passive"))
      (node (ref "RX") (pin "1") (pinfunction "1_1") (pintype "passive"))
      (node (ref "X2") (pin "15") (pinfunction "RXD_15") (pintype "input"))
    )
    (net (code "54") (name "Net-(X2-TXD)") (class "Default")
      (node (ref "J8") (pin "1") (pinfunction "1_1") (pintype "passive"))
      (node (ref "J8") (pin "2") (pinfunction "2_2") (pintype "passive"))
      (node (ref "J8") (pin "3") (pinfunction "3_3") (pintype "passive"))
      (node (ref "J8") (pin "4") (pinfunction "4_4") (pintype "passive"))
      (node (ref "TX") (pin "1") (pinfunction "1_1") (pintype "passive"))
      (node (ref "X2") (pin "16") (pinfunction "TXD_16") (pintype "output"))
    )
    (net (code "55") (name "VCC") (class "Default")
      (node (ref "DC") (pin "1") (pinfunction "VIN_1") (pintype "passive"))
      (node (ref "J1") (pin "1") (pinfunction "1_1") (pintype "passive"))
      (node (ref "U2") (pin "1") (pinfunction "IN_1") (pintype "input"))
      (node (ref "U2") (pin "3") (pinfunction "EN_3") (pintype "input"))
      (node (ref "X1") (pin "VBUS") (pinfunction "VBUS_VBUS") (pintype "power_in"))
    )
    (net (code "56") (name "VDD") (class "Default")
      (node (ref "DC") (pin "3") (pinfunction "VOUT_3") (pintype "passive"))
      (node (ref "J3") (pin "1") (pinfunction "1_1") (pintype "passive"))
      (node (ref "J3") (pin "10") (pinfunction "10_10") (pintype "passive"))
      (node (ref "J3") (pin "11") (pinfunction "11_11") (pintype "passive"))
      (node (ref "J3") (pin "12") (pinfunction "12_12") (pintype "passive"))
      (node (ref "J3") (pin "13") (pinfunction "13_13") (pintype "passive"))
      (node (ref "J3") (pin "14") (pinfunction "14_14") (pintype "passive"))
      (node (ref "J3") (pin "15") (pinfunction "15_15") (pintype "passive"))
      (node (ref "J3") (pin "16") (pinfunction "16_16") (pintype "passive"))
      (node (ref "J3") (pin "17") (pinfunction "17_17") (pintype "passive"))
      (node (ref "J3") (pin "18") (pinfunction "18_18") (pintype "passive"))
      (node (ref "J3") (pin "19") (pinfunction "19_19") (pintype "passive"))
      (node (ref "J3") (pin "2") (pinfunction "2_2") (pintype "passive"))
      (node (ref "J3") (pin "20") (pinfunction "20_20") (pintype "passive"))
      (node (ref "J3") (pin "21") (pinfunction "21_21") (pintype "passive"))
      (node (ref "J3") (pin "22") (pinfunction "22_22") (pintype "passive"))
      (node (ref "J3") (pin "23") (pinfunction "23_23") (pintype "passive"))
      (node (ref "J3") (pin "24") (pinfunction "24_24") (pintype "passive"))
      (node (ref "J3") (pin "25") (pinfunction "25_25") (pintype "passive"))
      (node (ref "J3") (pin "26") (pinfunction "26_26") (pintype "passive"))
      (node (ref "J3") (pin "27") (pinfunction "27_27") (pintype "passive"))
      (node (ref "J3") (pin "28") (pinfunction "28_28") (pintype "passive"))
      (node (ref "J3") (pin "29") (pinfunction "29_29") (pintype "passive"))
      (node (ref "J3") (pin "3") (pinfunction "3_3") (pintype "passive"))
      (node (ref "J3") (pin "4") (pinfunction "4_4") (pintype "passive"))
      (node (ref "J3") (pin "5") (pinfunction "5_5") (pintype "passive"))
      (node (ref "J3") (pin "6") (pinfunction "6_6") (pintype "passive"))
      (node (ref "J3") (pin "7") (pinfunction "7_7") (pintype "passive"))
      (node (ref "J3") (pin "8") (pinfunction "8_8") (pintype "passive"))
      (node (ref "J3") (pin "9") (pinfunction "9_9") (pintype "passive"))
      (node (ref "J5") (pin "1") (pinfunction "1_1") (pintype "passive"))
      (node (ref "J5") (pin "10") (pinfunction "10_10") (pintype "passive"))
      (node (ref "J5") (pin "11") (pinfunction "11_11") (pintype "passive"))
      (node (ref "J5") (pin "12") (pinfunction "12_12") (pintype "passive"))
      (node (ref "J5") (pin "13") (pinfunction "13_13") (pintype "passive"))
      (node (ref "J5") (pin "14") (pinfunction "14_14") (pintype "passive"))
      (node (ref "J5") (pin "15") (pinfunction "15_15") (pintype "passive"))
      (node (ref "J5") (pin "16") (pinfunction "16_16") (pintype "passive"))
      (node (ref "J5") (pin "17") (pinfunction "17_17") (pintype "passive"))
      (node (ref "J5") (pin "18") (pinfunction "18_18") (pintype "passive"))
      (node (ref "J5") (pin "19") (pinfunction "19_19") (pintype "passive"))
      (node (ref "J5") (pin "2") (pinfunction "2_2") (pintype "passive"))
      (node (ref "J5") (pin "20") (pinfunction "20_20") (pintype "passive"))
      (node (ref "J5") (pin "3") (pinfunction "3_3") (pintype "passive"))
      (node (ref "J5") (pin "4") (pinfunction "4_4") (pintype "passive"))
      (node (ref "J5") (pin "5") (pinfunction "5_5") (pintype "passive"))
      (node (ref "J5") (pin "6") (pinfunction "6_6") (pintype "passive"))
      (node (ref "J5") (pin "7") (pinfunction "7_7") (pintype "passive"))
      (node (ref "J5") (pin "8") (pinfunction "8_8") (pintype "passive"))
      (node (ref "J5") (pin "9") (pinfunction "9_9") (pintype "passive"))
      (node (ref "J7") (pin "1") (pinfunction "1_1") (pintype "passive"))
      (node (ref "J7") (pin "2") (pinfunction "2_2") (pintype "passive"))
      (node (ref "J7") (pin "3") (pinfunction "3_3") (pintype "passive"))
      (node (ref "J7") (pin "4") (pinfunction "4_4") (pintype "passive"))
      (node (ref "J7") (pin "5") (pinfunction "5_5") (pintype "passive"))
      (node (ref "U2") (pin "5") (pinfunction "OUT_5") (pintype "passive"))
      (node (ref "X2") (pin "8") (pinfunction "VCC_8") (pintype "power_in"))
    )
    (net (code "57") (name "unconnected-(U2-BP-Pad4)") (class "Default")
      (node (ref "U2") (pin "4") (pinfunction "BP_4") (pintype "input"))
    )
    (net (code "58") (name "unconnected-(X1-PadD+)") (class "Default")
      (node (ref "X1") (pin "D+") (pinfunction "D+_D+") (pintype "bidirectional"))
    )
    (net (code "59") (name "unconnected-(X1-PadD-)") (class "Default")
      (node (ref "X1") (pin "D-") (pinfunction "D-_D-") (pintype "bidirectional"))
    )
    (net (code "60") (name "unconnected-(X1-PadID)") (class "Default")
      (node (ref "X1") (pin "ID") (pinfunction "ID_ID") (pintype "bidirectional"))
    )
    (net (code "61") (name "unconnected-(X2-CLK-Pad20)") (class "Default")
      (node (ref "X2") (pin "20") (pinfunction "CLK_20") (pintype "bidirectional"))
    )
    (net (code "62") (name "unconnected-(X2-CS-Pad17)") (class "Default")
      (node (ref "X2") (pin "17") (pinfunction "CS_17") (pintype "bidirectional"))
    )
    (net (code "63") (name "unconnected-(X2-DI-Pad21)") (class "Default")
      (node (ref "X2") (pin "21") (pinfunction "DI_21") (pintype "bidirectional"))
    )
    (net (code "64") (name "unconnected-(X2-DO-Pad18)") (class "Default")
      (node (ref "X2") (pin "18") (pinfunction "DO_18") (pintype "bidirectional"))
    )
    (net (code "65") (name "unconnected-(X2-GPIO9-Pad22)") (class "Default")
      (node (ref "X2") (pin "22") (pinfunction "GPIO9_22") (pintype "bidirectional"))
    )
    (net (code "66") (name "unconnected-(X2-GPIO10-Pad19)") (class "Default")
      (node (ref "X2") (pin "19") (pinfunction "GPIO10_19") (pintype "bidirectional"))
    )
  )
)
